# Battery_Board_V3.net
KiCad netlist of a schematic drawn in EAGLE
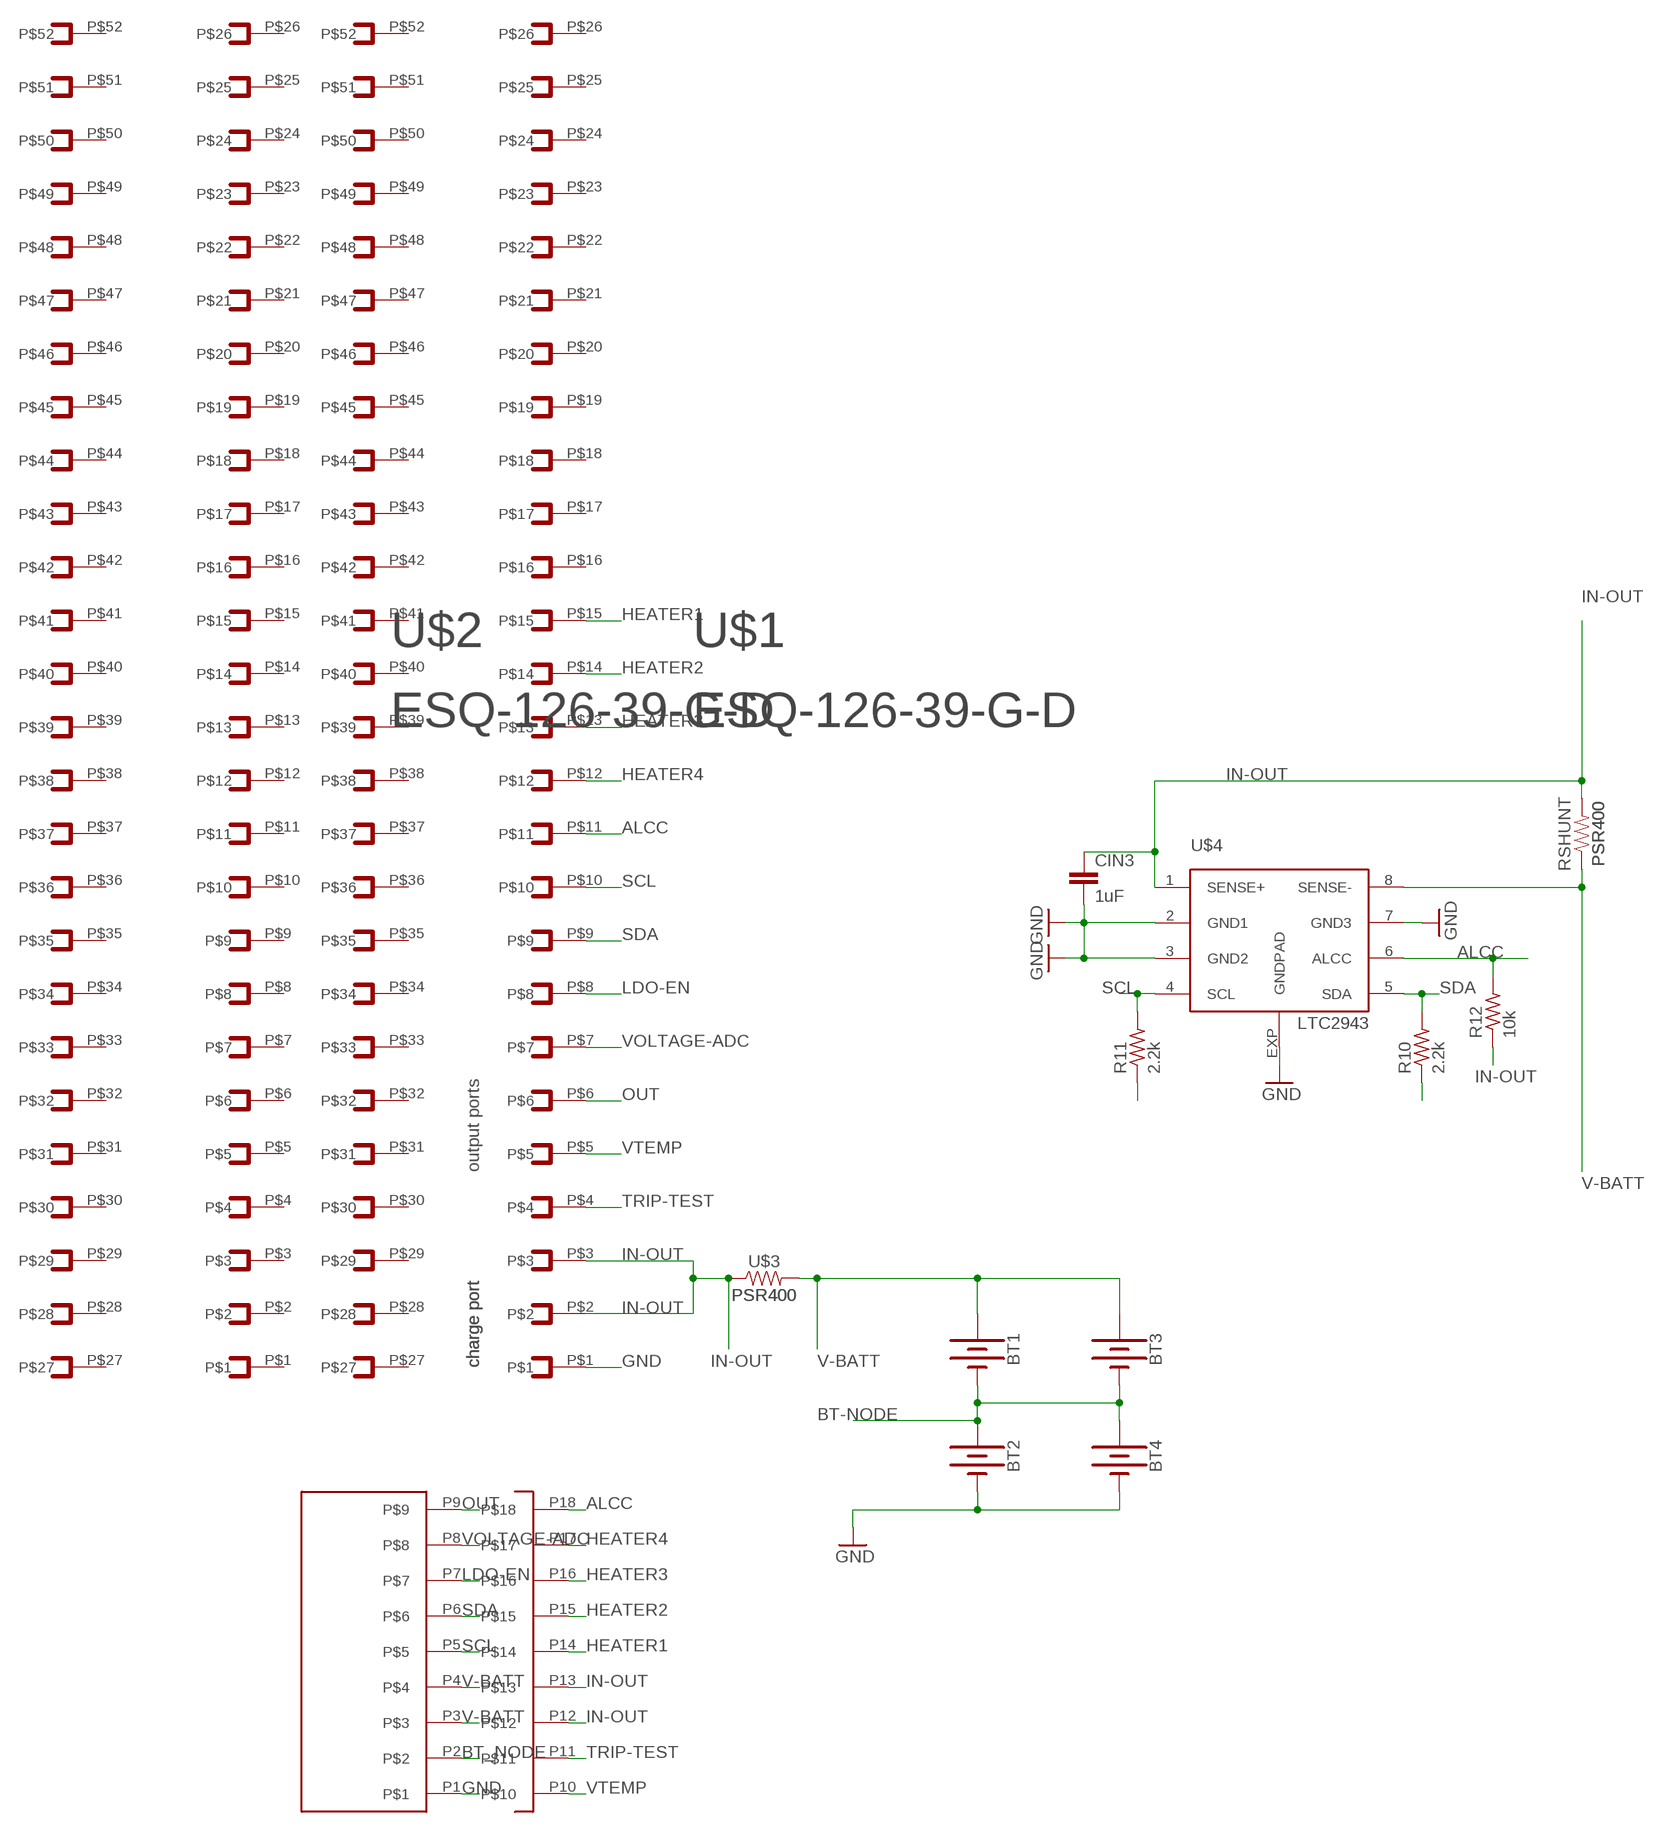
[diagram p0: schematic, sheet 1]

(export (version "E")
  (design (tool "Eeschema 10.0.6"))
  (components
    (comp (ref "BT1")
      (value "BATTERY-18650")
      (footprint "eagle-import:BATTERY_18650-HOLDER")
      (libsource (lib "eagle-import") (part "BATTERY-18650"))
    )
    (comp (ref "BT2")
      (value "BATTERY-18650")
      (footprint "eagle-import:BATTERY_18650-HOLDER")
      (libsource (lib "eagle-import") (part "BATTERY-18650"))
    )
    (comp (ref "BT3")
      (value "BATTERY-18650")
      (footprint "eagle-import:BATTERY_18650-HOLDER")
      (libsource (lib "eagle-import") (part "BATTERY-18650"))
    )
    (comp (ref "BT4")
      (value "BATTERY-18650")
      (footprint "eagle-import:BATTERY_18650-HOLDER")
      (libsource (lib "eagle-import") (part "BATTERY-18650"))
    )
    (comp (ref "CIN3")
      (value "1uF")
      (footprint "eagle-import:0402-CAP")
      (libsource (lib "eagle-import") (part ".1UF-CER"))
    )
    (comp (ref "R10")
      (value "2.2k")
      (footprint "eagle-import:R0805")
      (libsource (lib "eagle-import") (part "R-US_R0805"))
    )
    (comp (ref "R11")
      (value "2.2k")
      (footprint "eagle-import:R0805")
      (libsource (lib "eagle-import") (part "R-US_R0805"))
    )
    (comp (ref "R12")
      (value "10k")
      (footprint "eagle-import:R0805")
      (libsource (lib "eagle-import") (part "R-US_R0805"))
    )
    (comp (ref "RSHUNT")
      (value "PSR400")
      (footprint "eagle-import:PSR400")
      (libsource (lib "eagle-import") (part "PSR400"))
    )
    (comp (ref "U$1")
      (value "ESQ-126-39-G-D")
      (footprint "eagle-import:(RD)ESQ-126-39-G-D")
      (libsource (lib "eagle-import") (part "ESQ-126-39-G-D"))
    )
    (comp (ref "U$2")
      (value "ESQ-126-39-G-D")
      (footprint "eagle-import:(RD)ESQ-126-39-G-D")
      (libsource (lib "eagle-import") (part "ESQ-126-39-G-D"))
    )
    (comp (ref "U$3")
      (value "PSR400")
      (footprint "eagle-import:PSR400")
      (libsource (lib "eagle-import") (part "PSR400"))
    )
    (comp (ref "U$4")
      (value "LTC2943")
      (footprint "eagle-import:DFN8(3X3)LT")
      (libsource (lib "eagle-import") (part "LTC2943"))
    )
    (comp (ref "U$7")
      (value "FFC18")
      (footprint "eagle-import:FFC18")
      (libsource (lib "eagle-import") (part "FFC18"))
    )
  )
  (nets
    (net (code "1") (name "/ALCC") (class "Default")
      (node (ref "R12") (pin "2") (pinfunction "2_2") (pintype "passive"))
      (node (ref "U$1") (pin "P$11") (pinfunction "P$11_P$11") (pintype "bidirectional"))
      (node (ref "U$4") (pin "6") (pinfunction "ALCC_6") (pintype "bidirectional"))
      (node (ref "U$7") (pin "P18") (pinfunction "P$18_P18") (pintype "bidirectional"))
    )
    (net (code "2") (name "/BT-NODE") (class "Default")
      (node (ref "BT1") (pin "GND@1") (pinfunction "-_GND@1") (pintype "power_in"))
      (node (ref "BT2") (pin "PWR@1") (pinfunction "+_PWR@1") (pintype "power_in"))
      (node (ref "BT3") (pin "GND@1") (pinfunction "-_GND@1") (pintype "power_in"))
      (node (ref "BT4") (pin "PWR@1") (pinfunction "+_PWR@1") (pintype "power_in"))
    )
    (net (code "3") (name "/BT_NODE") (class "Default")
      (node (ref "U$7") (pin "P2") (pinfunction "P$2_P2") (pintype "bidirectional"))
    )
    (net (code "4") (name "/HEATER1") (class "Default")
      (node (ref "U$1") (pin "P$15") (pinfunction "P$15_P$15") (pintype "bidirectional"))
      (node (ref "U$7") (pin "P14") (pinfunction "P$14_P14") (pintype "bidirectional"))
    )
    (net (code "5") (name "/HEATER2") (class "Default")
      (node (ref "U$1") (pin "P$14") (pinfunction "P$14_P$14") (pintype "bidirectional"))
      (node (ref "U$7") (pin "P15") (pinfunction "P$15_P15") (pintype "bidirectional"))
    )
    (net (code "6") (name "/HEATER3") (class "Default")
      (node (ref "U$1") (pin "P$13") (pinfunction "P$13_P$13") (pintype "bidirectional"))
      (node (ref "U$7") (pin "P16") (pinfunction "P$16_P16") (pintype "bidirectional"))
    )
    (net (code "7") (name "/HEATER4") (class "Default")
      (node (ref "U$1") (pin "P$12") (pinfunction "P$12_P$12") (pintype "bidirectional"))
      (node (ref "U$7") (pin "P17") (pinfunction "P$17_P17") (pintype "bidirectional"))
    )
    (net (code "8") (name "/IN-OUT") (class "Default")
      (node (ref "CIN3") (pin "1") (pinfunction "1_1") (pintype "passive"))
      (node (ref "R10") (pin "1") (pinfunction "1_1") (pintype "passive"))
      (node (ref "R11") (pin "1") (pinfunction "1_1") (pintype "passive"))
      (node (ref "R12") (pin "1") (pinfunction "1_1") (pintype "passive"))
      (node (ref "RSHUNT") (pin "P$2") (pinfunction "2_P$2") (pintype "passive"))
      (node (ref "U$1") (pin "P$2") (pinfunction "P$2_P$2") (pintype "bidirectional"))
      (node (ref "U$1") (pin "P$3") (pinfunction "P$3_P$3") (pintype "bidirectional"))
      (node (ref "U$3") (pin "P$1") (pinfunction "1_P$1") (pintype "passive"))
      (node (ref "U$4") (pin "1") (pinfunction "SENSE+_1") (pintype "bidirectional"))
      (node (ref "U$7") (pin "P12") (pinfunction "P$12_P12") (pintype "bidirectional"))
      (node (ref "U$7") (pin "P13") (pinfunction "P$13_P13") (pintype "bidirectional"))
    )
    (net (code "9") (name "/LDO-EN") (class "Default")
      (node (ref "U$1") (pin "P$8") (pinfunction "P$8_P$8") (pintype "bidirectional"))
      (node (ref "U$7") (pin "P7") (pinfunction "P$7_P7") (pintype "bidirectional"))
    )
    (net (code "10") (name "/OUT") (class "Default")
      (node (ref "U$1") (pin "P$6") (pinfunction "P$6_P$6") (pintype "bidirectional"))
      (node (ref "U$7") (pin "P9") (pinfunction "P$9_P9") (pintype "bidirectional"))
    )
    (net (code "11") (name "/SCL") (class "Default")
      (node (ref "R11") (pin "2") (pinfunction "2_2") (pintype "passive"))
      (node (ref "U$1") (pin "P$10") (pinfunction "P$10_P$10") (pintype "bidirectional"))
      (node (ref "U$4") (pin "4") (pinfunction "SCL_4") (pintype "bidirectional"))
      (node (ref "U$7") (pin "P5") (pinfunction "P$5_P5") (pintype "bidirectional"))
    )
    (net (code "12") (name "/SDA") (class "Default")
      (node (ref "R10") (pin "2") (pinfunction "2_2") (pintype "passive"))
      (node (ref "U$1") (pin "P$9") (pinfunction "P$9_P$9") (pintype "bidirectional"))
      (node (ref "U$4") (pin "5") (pinfunction "SDA_5") (pintype "bidirectional"))
      (node (ref "U$7") (pin "P6") (pinfunction "P$6_P6") (pintype "bidirectional"))
    )
    (net (code "13") (name "/TRIP-TEST") (class "Default")
      (node (ref "U$1") (pin "P$4") (pinfunction "P$4_P$4") (pintype "bidirectional"))
      (node (ref "U$7") (pin "P11") (pinfunction "P$11_P11") (pintype "bidirectional"))
    )
    (net (code "14") (name "/V-BATT") (class "Default")
      (node (ref "BT1") (pin "PWR@1") (pinfunction "+_PWR@1") (pintype "power_in"))
      (node (ref "BT3") (pin "PWR@1") (pinfunction "+_PWR@1") (pintype "power_in"))
      (node (ref "RSHUNT") (pin "P$1") (pinfunction "1_P$1") (pintype "passive"))
      (node (ref "U$3") (pin "P$2") (pinfunction "2_P$2") (pintype "passive"))
      (node (ref "U$4") (pin "8") (pinfunction "SENSE-_8") (pintype "bidirectional"))
      (node (ref "U$7") (pin "P3") (pinfunction "P$3_P3") (pintype "bidirectional"))
      (node (ref "U$7") (pin "P4") (pinfunction "P$4_P4") (pintype "bidirectional"))
    )
    (net (code "15") (name "/VOLTAGE-ADC") (class "Default")
      (node (ref "U$1") (pin "P$7") (pinfunction "P$7_P$7") (pintype "bidirectional"))
      (node (ref "U$7") (pin "P8") (pinfunction "P$8_P8") (pintype "bidirectional"))
    )
    (net (code "16") (name "/VTEMP") (class "Default")
      (node (ref "U$1") (pin "P$5") (pinfunction "P$5_P$5") (pintype "bidirectional"))
      (node (ref "U$7") (pin "P10") (pinfunction "P$10_P10") (pintype "bidirectional"))
    )
    (net (code "17") (name "GND") (class "Default")
      (node (ref "BT2") (pin "GND@1") (pinfunction "-_GND@1") (pintype "power_in"))
      (node (ref "BT4") (pin "GND@1") (pinfunction "-_GND@1") (pintype "power_in"))
      (node (ref "CIN3") (pin "2") (pinfunction "2_2") (pintype "passive"))
      (node (ref "U$1") (pin "P$1") (pinfunction "P$1_P$1") (pintype "bidirectional"))
      (node (ref "U$4") (pin "2") (pinfunction "GND1_2") (pintype "bidirectional"))
      (node (ref "U$4") (pin "3") (pinfunction "GND2_3") (pintype "bidirectional"))
      (node (ref "U$4") (pin "7") (pinfunction "GND3_7") (pintype "bidirectional"))
      (node (ref "U$4") (pin "EXP") (pinfunction "GNDPAD_EXP") (pintype "bidirectional"))
      (node (ref "U$7") (pin "P1") (pinfunction "P$1_P1") (pintype "bidirectional"))
    )
    (net (code "18") (name "unconnected-(U$1-PadP$16)") (class "Default")
      (node (ref "U$1") (pin "P$16") (pinfunction "P$16_P$16") (pintype "bidirectional"))
    )
    (net (code "19") (name "unconnected-(U$1-PadP$17)") (class "Default")
      (node (ref "U$1") (pin "P$17") (pinfunction "P$17_P$17") (pintype "bidirectional"))
    )
    (net (code "20") (name "unconnected-(U$1-PadP$18)") (class "Default")
      (node (ref "U$1") (pin "P$18") (pinfunction "P$18_P$18") (pintype "bidirectional"))
    )
    (net (code "21") (name "unconnected-(U$1-PadP$19)") (class "Default")
      (node (ref "U$1") (pin "P$19") (pinfunction "P$19_P$19") (pintype "bidirectional"))
    )
    (net (code "22") (name "unconnected-(U$1-PadP$20)") (class "Default")
      (node (ref "U$1") (pin "P$20") (pinfunction "P$20_P$20") (pintype "bidirectional"))
    )
    (net (code "23") (name "unconnected-(U$1-PadP$21)") (class "Default")
      (node (ref "U$1") (pin "P$21") (pinfunction "P$21_P$21") (pintype "bidirectional"))
    )
    (net (code "24") (name "unconnected-(U$1-PadP$22)") (class "Default")
      (node (ref "U$1") (pin "P$22") (pinfunction "P$22_P$22") (pintype "bidirectional"))
    )
    (net (code "25") (name "unconnected-(U$1-PadP$23)") (class "Default")
      (node (ref "U$1") (pin "P$23") (pinfunction "P$23_P$23") (pintype "bidirectional"))
    )
    (net (code "26") (name "unconnected-(U$1-PadP$24)") (class "Default")
      (node (ref "U$1") (pin "P$24") (pinfunction "P$24_P$24") (pintype "bidirectional"))
    )
    (net (code "27") (name "unconnected-(U$1-PadP$25)") (class "Default")
      (node (ref "U$1") (pin "P$25") (pinfunction "P$25_P$25") (pintype "bidirectional"))
    )
    (net (code "28") (name "unconnected-(U$1-PadP$26)") (class "Default")
      (node (ref "U$1") (pin "P$26") (pinfunction "P$26_P$26") (pintype "bidirectional"))
    )
    (net (code "29") (name "unconnected-(U$1-PadP$27)") (class "Default")
      (node (ref "U$1") (pin "P$27") (pinfunction "P$27_P$27") (pintype "bidirectional"))
    )
    (net (code "30") (name "unconnected-(U$1-PadP$28)") (class "Default")
      (node (ref "U$1") (pin "P$28") (pinfunction "P$28_P$28") (pintype "bidirectional"))
    )
    (net (code "31") (name "unconnected-(U$1-PadP$29)") (class "Default")
      (node (ref "U$1") (pin "P$29") (pinfunction "P$29_P$29") (pintype "bidirectional"))
    )
    (net (code "32") (name "unconnected-(U$1-PadP$30)") (class "Default")
      (node (ref "U$1") (pin "P$30") (pinfunction "P$30_P$30") (pintype "bidirectional"))
    )
    (net (code "33") (name "unconnected-(U$1-PadP$31)") (class "Default")
      (node (ref "U$1") (pin "P$31") (pinfunction "P$31_P$31") (pintype "bidirectional"))
    )
    (net (code "34") (name "unconnected-(U$1-PadP$32)") (class "Default")
      (node (ref "U$1") (pin "P$32") (pinfunction "P$32_P$32") (pintype "bidirectional"))
    )
    (net (code "35") (name "unconnected-(U$1-PadP$33)") (class "Default")
      (node (ref "U$1") (pin "P$33") (pinfunction "P$33_P$33") (pintype "bidirectional"))
    )
    (net (code "36") (name "unconnected-(U$1-PadP$34)") (class "Default")
      (node (ref "U$1") (pin "P$34") (pinfunction "P$34_P$34") (pintype "bidirectional"))
    )
    (net (code "37") (name "unconnected-(U$1-PadP$35)") (class "Default")
      (node (ref "U$1") (pin "P$35") (pinfunction "P$35_P$35") (pintype "bidirectional"))
    )
    (net (code "38") (name "unconnected-(U$1-PadP$36)") (class "Default")
      (node (ref "U$1") (pin "P$36") (pinfunction "P$36_P$36") (pintype "bidirectional"))
    )
    (net (code "39") (name "unconnected-(U$1-PadP$37)") (class "Default")
      (node (ref "U$1") (pin "P$37") (pinfunction "P$37_P$37") (pintype "bidirectional"))
    )
    (net (code "40") (name "unconnected-(U$1-PadP$38)") (class "Default")
      (node (ref "U$1") (pin "P$38") (pinfunction "P$38_P$38") (pintype "bidirectional"))
    )
    (net (code "41") (name "unconnected-(U$1-PadP$39)") (class "Default")
      (node (ref "U$1") (pin "P$39") (pinfunction "P$39_P$39") (pintype "bidirectional"))
    )
    (net (code "42") (name "unconnected-(U$1-PadP$40)") (class "Default")
      (node (ref "U$1") (pin "P$40") (pinfunction "P$40_P$40") (pintype "bidirectional"))
    )
    (net (code "43") (name "unconnected-(U$1-PadP$41)") (class "Default")
      (node (ref "U$1") (pin "P$41") (pinfunction "P$41_P$41") (pintype "bidirectional"))
    )
    (net (code "44") (name "unconnected-(U$1-PadP$42)") (class "Default")
      (node (ref "U$1") (pin "P$42") (pinfunction "P$42_P$42") (pintype "bidirectional"))
    )
    (net (code "45") (name "unconnected-(U$1-PadP$43)") (class "Default")
      (node (ref "U$1") (pin "P$43") (pinfunction "P$43_P$43") (pintype "bidirectional"))
    )
    (net (code "46") (name "unconnected-(U$1-PadP$44)") (class "Default")
      (node (ref "U$1") (pin "P$44") (pinfunction "P$44_P$44") (pintype "bidirectional"))
    )
    (net (code "47") (name "unconnected-(U$1-PadP$45)") (class "Default")
      (node (ref "U$1") (pin "P$45") (pinfunction "P$45_P$45") (pintype "bidirectional"))
    )
    (net (code "48") (name "unconnected-(U$1-PadP$46)") (class "Default")
      (node (ref "U$1") (pin "P$46") (pinfunction "P$46_P$46") (pintype "bidirectional"))
    )
    (net (code "49") (name "unconnected-(U$1-PadP$47)") (class "Default")
      (node (ref "U$1") (pin "P$47") (pinfunction "P$47_P$47") (pintype "bidirectional"))
    )
    (net (code "50") (name "unconnected-(U$1-PadP$48)") (class "Default")
      (node (ref "U$1") (pin "P$48") (pinfunction "P$48_P$48") (pintype "bidirectional"))
    )
    (net (code "51") (name "unconnected-(U$1-PadP$49)") (class "Default")
      (node (ref "U$1") (pin "P$49") (pinfunction "P$49_P$49") (pintype "bidirectional"))
    )
    (net (code "52") (name "unconnected-(U$1-PadP$50)") (class "Default")
      (node (ref "U$1") (pin "P$50") (pinfunction "P$50_P$50") (pintype "bidirectional"))
    )
    (net (code "53") (name "unconnected-(U$1-PadP$51)") (class "Default")
      (node (ref "U$1") (pin "P$51") (pinfunction "P$51_P$51") (pintype "bidirectional"))
    )
    (net (code "54") (name "unconnected-(U$1-PadP$52)") (class "Default")
      (node (ref "U$1") (pin "P$52") (pinfunction "P$52_P$52") (pintype "bidirectional"))
    )
    (net (code "55") (name "unconnected-(U$2-PadP$1)") (class "Default")
      (node (ref "U$2") (pin "P$1") (pinfunction "P$1_P$1") (pintype "bidirectional"))
    )
    (net (code "56") (name "unconnected-(U$2-PadP$2)") (class "Default")
      (node (ref "U$2") (pin "P$2") (pinfunction "P$2_P$2") (pintype "bidirectional"))
    )
    (net (code "57") (name "unconnected-(U$2-PadP$3)") (class "Default")
      (node (ref "U$2") (pin "P$3") (pinfunction "P$3_P$3") (pintype "bidirectional"))
    )
    (net (code "58") (name "unconnected-(U$2-PadP$4)") (class "Default")
      (node (ref "U$2") (pin "P$4") (pinfunction "P$4_P$4") (pintype "bidirectional"))
    )
    (net (code "59") (name "unconnected-(U$2-PadP$5)") (class "Default")
      (node (ref "U$2") (pin "P$5") (pinfunction "P$5_P$5") (pintype "bidirectional"))
    )
    (net (code "60") (name "unconnected-(U$2-PadP$6)") (class "Default")
      (node (ref "U$2") (pin "P$6") (pinfunction "P$6_P$6") (pintype "bidirectional"))
    )
    (net (code "61") (name "unconnected-(U$2-PadP$7)") (class "Default")
      (node (ref "U$2") (pin "P$7") (pinfunction "P$7_P$7") (pintype "bidirectional"))
    )
    (net (code "62") (name "unconnected-(U$2-PadP$8)") (class "Default")
      (node (ref "U$2") (pin "P$8") (pinfunction "P$8_P$8") (pintype "bidirectional"))
    )
    (net (code "63") (name "unconnected-(U$2-PadP$9)") (class "Default")
      (node (ref "U$2") (pin "P$9") (pinfunction "P$9_P$9") (pintype "bidirectional"))
    )
    (net (code "64") (name "unconnected-(U$2-PadP$10)") (class "Default")
      (node (ref "U$2") (pin "P$10") (pinfunction "P$10_P$10") (pintype "bidirectional"))
    )
    (net (code "65") (name "unconnected-(U$2-PadP$11)") (class "Default")
      (node (ref "U$2") (pin "P$11") (pinfunction "P$11_P$11") (pintype "bidirectional"))
    )
    (net (code "66") (name "unconnected-(U$2-PadP$12)") (class "Default")
      (node (ref "U$2") (pin "P$12") (pinfunction "P$12_P$12") (pintype "bidirectional"))
    )
    (net (code "67") (name "unconnected-(U$2-PadP$13)") (class "Default")
      (node (ref "U$2") (pin "P$13") (pinfunction "P$13_P$13") (pintype "bidirectional"))
    )
    (net (code "68") (name "unconnected-(U$2-PadP$14)") (class "Default")
      (node (ref "U$2") (pin "P$14") (pinfunction "P$14_P$14") (pintype "bidirectional"))
    )
    (net (code "69") (name "unconnected-(U$2-PadP$15)") (class "Default")
      (node (ref "U$2") (pin "P$15") (pinfunction "P$15_P$15") (pintype "bidirectional"))
    )
    (net (code "70") (name "unconnected-(U$2-PadP$16)") (class "Default")
      (node (ref "U$2") (pin "P$16") (pinfunction "P$16_P$16") (pintype "bidirectional"))
    )
    (net (code "71") (name "unconnected-(U$2-PadP$17)") (class "Default")
      (node (ref "U$2") (pin "P$17") (pinfunction "P$17_P$17") (pintype "bidirectional"))
    )
    (net (code "72") (name "unconnected-(U$2-PadP$18)") (class "Default")
      (node (ref "U$2") (pin "P$18") (pinfunction "P$18_P$18") (pintype "bidirectional"))
    )
    (net (code "73") (name "unconnected-(U$2-PadP$19)") (class "Default")
      (node (ref "U$2") (pin "P$19") (pinfunction "P$19_P$19") (pintype "bidirectional"))
    )
    (net (code "74") (name "unconnected-(U$2-PadP$20)") (class "Default")
      (node (ref "U$2") (pin "P$20") (pinfunction "P$20_P$20") (pintype "bidirectional"))
    )
    (net (code "75") (name "unconnected-(U$2-PadP$21)") (class "Default")
      (node (ref "U$2") (pin "P$21") (pinfunction "P$21_P$21") (pintype "bidirectional"))
    )
    (net (code "76") (name "unconnected-(U$2-PadP$22)") (class "Default")
      (node (ref "U$2") (pin "P$22") (pinfunction "P$22_P$22") (pintype "bidirectional"))
    )
    (net (code "77") (name "unconnected-(U$2-PadP$23)") (class "Default")
      (node (ref "U$2") (pin "P$23") (pinfunction "P$23_P$23") (pintype "bidirectional"))
    )
    (net (code "78") (name "unconnected-(U$2-PadP$24)") (class "Default")
      (node (ref "U$2") (pin "P$24") (pinfunction "P$24_P$24") (pintype "bidirectional"))
    )
    (net (code "79") (name "unconnected-(U$2-PadP$25)") (class "Default")
      (node (ref "U$2") (pin "P$25") (pinfunction "P$25_P$25") (pintype "bidirectional"))
    )
    (net (code "80") (name "unconnected-(U$2-PadP$26)") (class "Default")
      (node (ref "U$2") (pin "P$26") (pinfunction "P$26_P$26") (pintype "bidirectional"))
    )
    (net (code "81") (name "unconnected-(U$2-PadP$27)") (class "Default")
      (node (ref "U$2") (pin "P$27") (pinfunction "P$27_P$27") (pintype "bidirectional"))
    )
    (net (code "82") (name "unconnected-(U$2-PadP$28)") (class "Default")
      (node (ref "U$2") (pin "P$28") (pinfunction "P$28_P$28") (pintype "bidirectional"))
    )
    (net (code "83") (name "unconnected-(U$2-PadP$29)") (class "Default")
      (node (ref "U$2") (pin "P$29") (pinfunction "P$29_P$29") (pintype "bidirectional"))
    )
    (net (code "84") (name "unconnected-(U$2-PadP$30)") (class "Default")
      (node (ref "U$2") (pin "P$30") (pinfunction "P$30_P$30") (pintype "bidirectional"))
    )
    (net (code "85") (name "unconnected-(U$2-PadP$31)") (class "Default")
      (node (ref "U$2") (pin "P$31") (pinfunction "P$31_P$31") (pintype "bidirectional"))
    )
    (net (code "86") (name "unconnected-(U$2-PadP$32)") (class "Default")
      (node (ref "U$2") (pin "P$32") (pinfunction "P$32_P$32") (pintype "bidirectional"))
    )
    (net (code "87") (name "unconnected-(U$2-PadP$33)") (class "Default")
      (node (ref "U$2") (pin "P$33") (pinfunction "P$33_P$33") (pintype "bidirectional"))
    )
    (net (code "88") (name "unconnected-(U$2-PadP$34)") (class "Default")
      (node (ref "U$2") (pin "P$34") (pinfunction "P$34_P$34") (pintype "bidirectional"))
    )
    (net (code "89") (name "unconnected-(U$2-PadP$35)") (class "Default")
      (node (ref "U$2") (pin "P$35") (pinfunction "P$35_P$35") (pintype "bidirectional"))
    )
    (net (code "90") (name "unconnected-(U$2-PadP$36)") (class "Default")
      (node (ref "U$2") (pin "P$36") (pinfunction "P$36_P$36") (pintype "bidirectional"))
    )
    (net (code "91") (name "unconnected-(U$2-PadP$37)") (class "Default")
      (node (ref "U$2") (pin "P$37") (pinfunction "P$37_P$37") (pintype "bidirectional"))
    )
    (net (code "92") (name "unconnected-(U$2-PadP$38)") (class "Default")
      (node (ref "U$2") (pin "P$38") (pinfunction "P$38_P$38") (pintype "bidirectional"))
    )
    (net (code "93") (name "unconnected-(U$2-PadP$39)") (class "Default")
      (node (ref "U$2") (pin "P$39") (pinfunction "P$39_P$39") (pintype "bidirectional"))
    )
    (net (code "94") (name "unconnected-(U$2-PadP$40)") (class "Default")
      (node (ref "U$2") (pin "P$40") (pinfunction "P$40_P$40") (pintype "bidirectional"))
    )
    (net (code "95") (name "unconnected-(U$2-PadP$41)") (class "Default")
      (node (ref "U$2") (pin "P$41") (pinfunction "P$41_P$41") (pintype "bidirectional"))
    )
    (net (code "96") (name "unconnected-(U$2-PadP$42)") (class "Default")
      (node (ref "U$2") (pin "P$42") (pinfunction "P$42_P$42") (pintype "bidirectional"))
    )
    (net (code "97") (name "unconnected-(U$2-PadP$43)") (class "Default")
      (node (ref "U$2") (pin "P$43") (pinfunction "P$43_P$43") (pintype "bidirectional"))
    )
    (net (code "98") (name "unconnected-(U$2-PadP$44)") (class "Default")
      (node (ref "U$2") (pin "P$44") (pinfunction "P$44_P$44") (pintype "bidirectional"))
    )
    (net (code "99") (name "unconnected-(U$2-PadP$45)") (class "Default")
      (node (ref "U$2") (pin "P$45") (pinfunction "P$45_P$45") (pintype "bidirectional"))
    )
    (net (code "100") (name "unconnected-(U$2-PadP$46)") (class "Default")
      (node (ref "U$2") (pin "P$46") (pinfunction "P$46_P$46") (pintype "bidirectional"))
    )
    (net (code "101") (name "unconnected-(U$2-PadP$47)") (class "Default")
      (node (ref "U$2") (pin "P$47") (pinfunction "P$47_P$47") (pintype "bidirectional"))
    )
    (net (code "102") (name "unconnected-(U$2-PadP$48)") (class "Default")
      (node (ref "U$2") (pin "P$48") (pinfunction "P$48_P$48") (pintype "bidirectional"))
    )
    (net (code "103") (name "unconnected-(U$2-PadP$49)") (class "Default")
      (node (ref "U$2") (pin "P$49") (pinfunction "P$49_P$49") (pintype "bidirectional"))
    )
    (net (code "104") (name "unconnected-(U$2-PadP$50)") (class "Default")
      (node (ref "U$2") (pin "P$50") (pinfunction "P$50_P$50") (pintype "bidirectional"))
    )
    (net (code "105") (name "unconnected-(U$2-PadP$51)") (class "Default")
      (node (ref "U$2") (pin "P$51") (pinfunction "P$51_P$51") (pintype "bidirectional"))
    )
    (net (code "106") (name "unconnected-(U$2-PadP$52)") (class "Default")
      (node (ref "U$2") (pin "P$52") (pinfunction "P$52_P$52") (pintype "bidirectional"))
    )
  )
)
